# HIM.net
KiCad netlist of a schematic drawn in Altium Designer
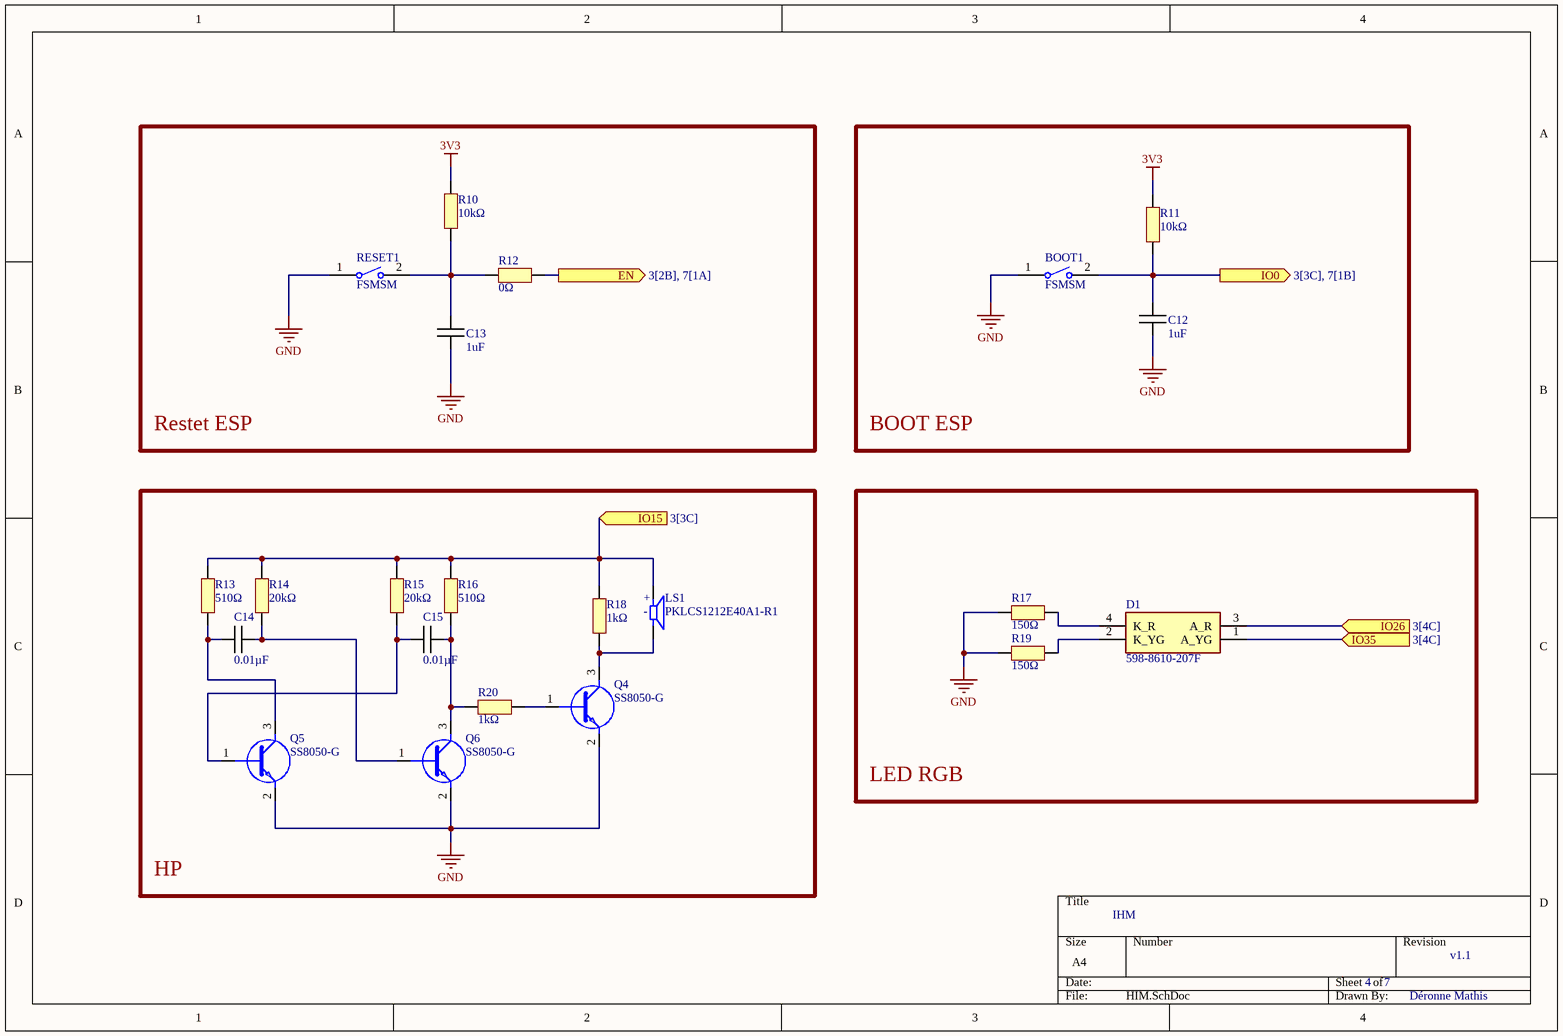
[diagram p0: HIM.SchDoc]

(export (version "E")
  (design (tool "Eeschema 10.0.6"))
  (components
    (comp (ref "BOOT1")
      (value "FSMSM")
      (footprint "TECO-FSMSM-2_V")
      (description "FSMSM Push Button Switch, 50 mA, -35 to 85 degC, 2-Pin SMD, RoHS, Bulk")
      (fields (field (name "MANUFACTURER") "TE Connectivity"))
      (libsource (lib "SCHLibrary") (part "CMP-2000-07511-1"))
    )
    (comp (ref "C12")
      (value "1uF")
      (footprint "CAPC1005X06N")
      (libsource (lib "SCHLibrary") (part "Capacitor"))
    )
    (comp (ref "C13")
      (value "1uF")
      (footprint "CAPC1005X06N")
      (libsource (lib "SCHLibrary") (part "Capacitor"))
    )
    (comp (ref "C14")
      (value "0.01µF")
      (footprint "CAPC1005X06N")
      (libsource (lib "SCHLibrary") (part "Capacitor"))
    )
    (comp (ref "C15")
      (value "0.01µF")
      (footprint "CAPC1005X06N")
      (libsource (lib "SCHLibrary") (part "Capacitor"))
    )
    (comp (ref "D1")
      (value "598-8610-207F")
      (footprint "5988610207F")
      (description "Standard LEDs - SMD Red/Green WC 80/50mcd 645/570nm")
      (fields (field (name "MOUSER PART NUMBER") "645-598-8610-207F"))
      (libsource (lib "SCHLibrary") (part "598-8610-207F"))
    )
    (comp (ref "LS1")
      (value "PKLCS1212E40A1-R1")
      (footprint "SPKR_PKLCS1212E40A1-R1")
      (description "Buzzers Transducer, Externally Driven Piezo 1.5V 2kHz 70dB @ 1.5V, 10cm Surface Mount Solder Pads")
      (fields (field (name "MF") "Murata Electronics"))
      (libsource (lib "SCHLibrary") (part "PKLCS1212E40A1-R1"))
    )
    (comp (ref "Q4")
      (value "SS8050-G")
      (footprint "SS8050-G")
      (description "Bipolar Transistors - BJT NPN TRANSISTOR 1.5A 40V")
      (libsource (lib "SCHLibrary") (part "SS8050-G"))
    )
    (comp (ref "Q5")
      (value "SS8050-G")
      (footprint "SS8050-G")
      (description "Bipolar Transistors - BJT NPN TRANSISTOR 1.5A 40V")
      (libsource (lib "SCHLibrary") (part "SS8050-G"))
    )
    (comp (ref "Q6")
      (value "SS8050-G")
      (footprint "SS8050-G")
      (description "Bipolar Transistors - BJT NPN TRANSISTOR 1.5A 40V")
      (libsource (lib "SCHLibrary") (part "SS8050-G"))
    )
    (comp (ref "R10")
      (value "10kΩ")
      (footprint "RESC1005X06N")
      (libsource (lib "SCHLibrary") (part "Resistor"))
    )
    (comp (ref "R11")
      (value "10kΩ")
      (footprint "RESC1005X06N")
      (libsource (lib "SCHLibrary") (part "Resistor"))
    )
    (comp (ref "R12") (value "0Ω") (footprint "RESC1005X06N") (libsource (lib "") (part "Resistor_1")))
    (comp (ref "R13")
      (value "510Ω")
      (footprint "RESC1005X06N")
      (libsource (lib "SCHLibrary") (part "Resistor"))
    )
    (comp (ref "R14")
      (value "20kΩ")
      (footprint "RESC1005X06N")
      (libsource (lib "SCHLibrary") (part "Resistor"))
    )
    (comp (ref "R15")
      (value "20kΩ")
      (footprint "RESC1005X06N")
      (libsource (lib "SCHLibrary") (part "Resistor"))
    )
    (comp (ref "R16")
      (value "510Ω")
      (footprint "RESC1005X06N")
      (libsource (lib "SCHLibrary") (part "Resistor"))
    )
    (comp (ref "R17") (value "150Ω") (footprint "RESC1005X06N") (libsource (lib "") (part "Resistor_1")))
    (comp (ref "R18")
      (value "1kΩ")
      (footprint "RESC1005X06N")
      (libsource (lib "SCHLibrary") (part "Resistor"))
    )
    (comp (ref "R19") (value "150Ω") (footprint "RESC1005X06N") (libsource (lib "") (part "Resistor_1")))
    (comp (ref "R20") (value "1kΩ") (footprint "RESC1005X06N") (libsource (lib "") (part "Resistor_1")))
    (comp (ref "RESET1")
      (value "FSMSM")
      (footprint "TECO-FSMSM-2_V")
      (description "FSMSM Push Button Switch, 50 mA, -35 to 85 degC, 2-Pin SMD, RoHS, Bulk")
      (fields (field (name "MANUFACTURER") "TE Connectivity"))
      (libsource (lib "SCHLibrary") (part "CMP-2000-07511-1"))
    )
  )
  (nets
    (net (code "1") (name "/EN") (class "Default")
      (node (ref "R12") (pin "2") (pinfunction "2_2") (pintype "passive"))
    )
    (net (code "2") (name "/IO0") (class "Default")
      (node (ref "BOOT1") (pin "2") (pinfunction "2_2") (pintype "passive"))
      (node (ref "C12") (pin "1") (pinfunction "1_1") (pintype "passive"))
      (node (ref "R11") (pin "1") (pinfunction "1_1") (pintype "passive"))
    )
    (net (code "3") (name "/IO15") (class "Default")
      (node (ref "LS1") (pin "P") (pinfunction "P_P") (pintype "passive"))
      (node (ref "R13") (pin "2") (pinfunction "2_2") (pintype "passive"))
      (node (ref "R14") (pin "2") (pinfunction "2_2") (pintype "passive"))
      (node (ref "R15") (pin "2") (pinfunction "2_2") (pintype "passive"))
      (node (ref "R16") (pin "2") (pinfunction "2_2") (pintype "passive"))
      (node (ref "R18") (pin "2") (pinfunction "2_2") (pintype "passive"))
    )
    (net (code "4") (name "/IO26") (class "Default")
      (node (ref "D1") (pin "3") (pinfunction "A_R_3") (pintype "passive"))
    )
    (net (code "5") (name "/IO35") (class "Default")
      (node (ref "D1") (pin "1") (pinfunction "A_YG_1") (pintype "passive"))
    )
    (net (code "6") (name "3V3") (class "Default")
      (node (ref "R10") (pin "2") (pinfunction "2_2") (pintype "passive"))
      (node (ref "R11") (pin "2") (pinfunction "2_2") (pintype "passive"))
    )
    (net (code "7") (name "GND") (class "Default")
      (node (ref "BOOT1") (pin "1") (pinfunction "1_1") (pintype "passive"))
      (node (ref "C12") (pin "2") (pinfunction "2_2") (pintype "passive"))
      (node (ref "C13") (pin "2") (pinfunction "2_2") (pintype "passive"))
      (node (ref "Q4") (pin "2") (pinfunction "E_2") (pintype "passive"))
      (node (ref "Q5") (pin "2") (pinfunction "E_2") (pintype "passive"))
      (node (ref "Q6") (pin "2") (pinfunction "E_2") (pintype "passive"))
      (node (ref "R17") (pin "1") (pinfunction "1_1") (pintype "passive"))
      (node (ref "R19") (pin "1") (pinfunction "1_1") (pintype "passive"))
      (node (ref "RESET1") (pin "1") (pinfunction "1_1") (pintype "passive"))
    )
    (net (code "8") (name "Net-(C13-Pad1)") (class "Default")
      (node (ref "C13") (pin "1") (pinfunction "1_1") (pintype "passive"))
      (node (ref "R10") (pin "1") (pinfunction "1_1") (pintype "passive"))
      (node (ref "R12") (pin "1") (pinfunction "1_1") (pintype "passive"))
      (node (ref "RESET1") (pin "2") (pinfunction "2_2") (pintype "passive"))
    )
    (net (code "9") (name "Net-(D1-K_R)") (class "Default")
      (node (ref "D1") (pin "4") (pinfunction "K_R_4") (pintype "passive"))
      (node (ref "R17") (pin "2") (pinfunction "2_2") (pintype "passive"))
    )
    (net (code "10") (name "Net-(D1-K_YG)") (class "Default")
      (node (ref "D1") (pin "2") (pinfunction "K_YG_2") (pintype "passive"))
      (node (ref "R19") (pin "2") (pinfunction "2_2") (pintype "passive"))
    )
    (net (code "11") (name "Net-(Q4-B)") (class "Default")
      (node (ref "Q4") (pin "1") (pinfunction "B_1") (pintype "passive"))
      (node (ref "R20") (pin "2") (pinfunction "2_2") (pintype "passive"))
    )
    (net (code "12") (name "Net-(Q4-C)") (class "Default")
      (node (ref "LS1") (pin "N") (pinfunction "N_N") (pintype "passive"))
      (node (ref "Q4") (pin "3") (pinfunction "C_3") (pintype "passive"))
      (node (ref "R18") (pin "1") (pinfunction "1_1") (pintype "passive"))
    )
    (net (code "13") (name "Net-(Q5-B)") (class "Default")
      (node (ref "C15") (pin "1") (pinfunction "1_1") (pintype "passive"))
      (node (ref "Q5") (pin "1") (pinfunction "B_1") (pintype "passive"))
      (node (ref "R15") (pin "1") (pinfunction "1_1") (pintype "passive"))
    )
    (net (code "14") (name "Net-(Q5-C)") (class "Default")
      (node (ref "C14") (pin "1") (pinfunction "1_1") (pintype "passive"))
      (node (ref "Q5") (pin "3") (pinfunction "C_3") (pintype "passive"))
      (node (ref "R13") (pin "1") (pinfunction "1_1") (pintype "passive"))
    )
    (net (code "15") (name "Net-(Q6-B)") (class "Default")
      (node (ref "C14") (pin "2") (pinfunction "2_2") (pintype "passive"))
      (node (ref "Q6") (pin "1") (pinfunction "B_1") (pintype "passive"))
      (node (ref "R14") (pin "1") (pinfunction "1_1") (pintype "passive"))
    )
    (net (code "16") (name "Net-(Q6-C)") (class "Default")
      (node (ref "C15") (pin "2") (pinfunction "2_2") (pintype "passive"))
      (node (ref "Q6") (pin "3") (pinfunction "C_3") (pintype "passive"))
      (node (ref "R16") (pin "1") (pinfunction "1_1") (pintype "passive"))
      (node (ref "R20") (pin "1") (pinfunction "1_1") (pintype "passive"))
    )
  )
)
